# Power_board.net
KiCad netlist of a schematic drawn in EAGLE
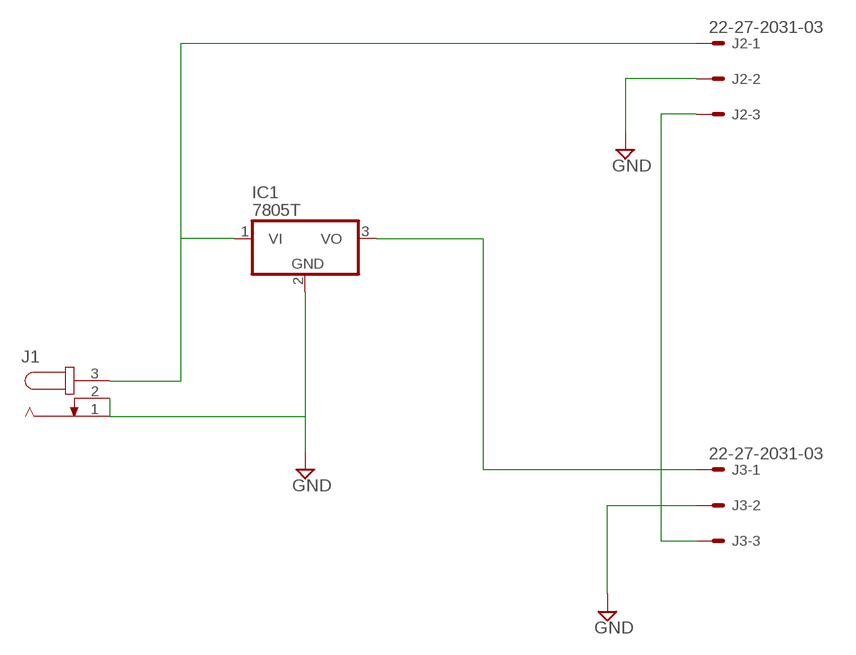
[diagram p0: schematic, sheet 1]

(export (version "E")
  (design (tool "Eeschema 10.0.6"))
  (components
    (comp (ref "IC1")
      (value "7805T")
      (footprint "eagle-import:TO220H")
      (libsource (lib "eagle-import") (part "78T05"))
    )
    (comp (ref "J1")
      (value "JACK-PLUG0")
      (footprint "eagle-import:SPC4077")
      (libsource (lib "eagle-import") (part "JACK-PLUG0"))
    )
    (comp (ref "J2")
      (value "22-27-2031-03")
      (footprint "eagle-import:6410-03")
      (libsource (lib "eagle-import") (part "22-?-0327-2031"))
    )
    (comp (ref "J3")
      (value "22-27-2031-03")
      (footprint "eagle-import:6410-03")
      (libsource (lib "eagle-import") (part "22-?-0327-2031"))
    )
  )
  (nets
    (net (code "1") (name "GND") (class "Default")
      (node (ref "IC1") (pin "2") (pinfunction "GND_2") (pintype "passive"))
      (node (ref "J1") (pin "1") (pinfunction "1_1") (pintype "passive"))
      (node (ref "J1") (pin "2") (pinfunction "2_2") (pintype "passive"))
      (node (ref "J2") (pin "2") (pinfunction "S_2") (pintype "passive"))
      (node (ref "J3") (pin "2") (pinfunction "S_2") (pintype "passive"))
    )
    (net (code "2") (name "Net-(IC1-VI)") (class "Default")
      (node (ref "IC1") (pin "1") (pinfunction "VI_1") (pintype "input"))
      (node (ref "J1") (pin "3") (pinfunction "3_3") (pintype "passive"))
      (node (ref "J2") (pin "1") (pinfunction "S_1") (pintype "passive"))
    )
    (net (code "3") (name "Net-(IC1-VO)") (class "Default")
      (node (ref "IC1") (pin "3") (pinfunction "VO_3") (pintype "passive"))
      (node (ref "J3") (pin "1") (pinfunction "S_1") (pintype "passive"))
    )
    (net (code "4") (name "Net-(J2C-S)") (class "Default")
      (node (ref "J2") (pin "3") (pinfunction "S_3") (pintype "passive"))
      (node (ref "J3") (pin "3") (pinfunction "S_3") (pintype "passive"))
    )
  )
)
